# booz_imu_h.net
KiCad netlist of a schematic drawn in EAGLE
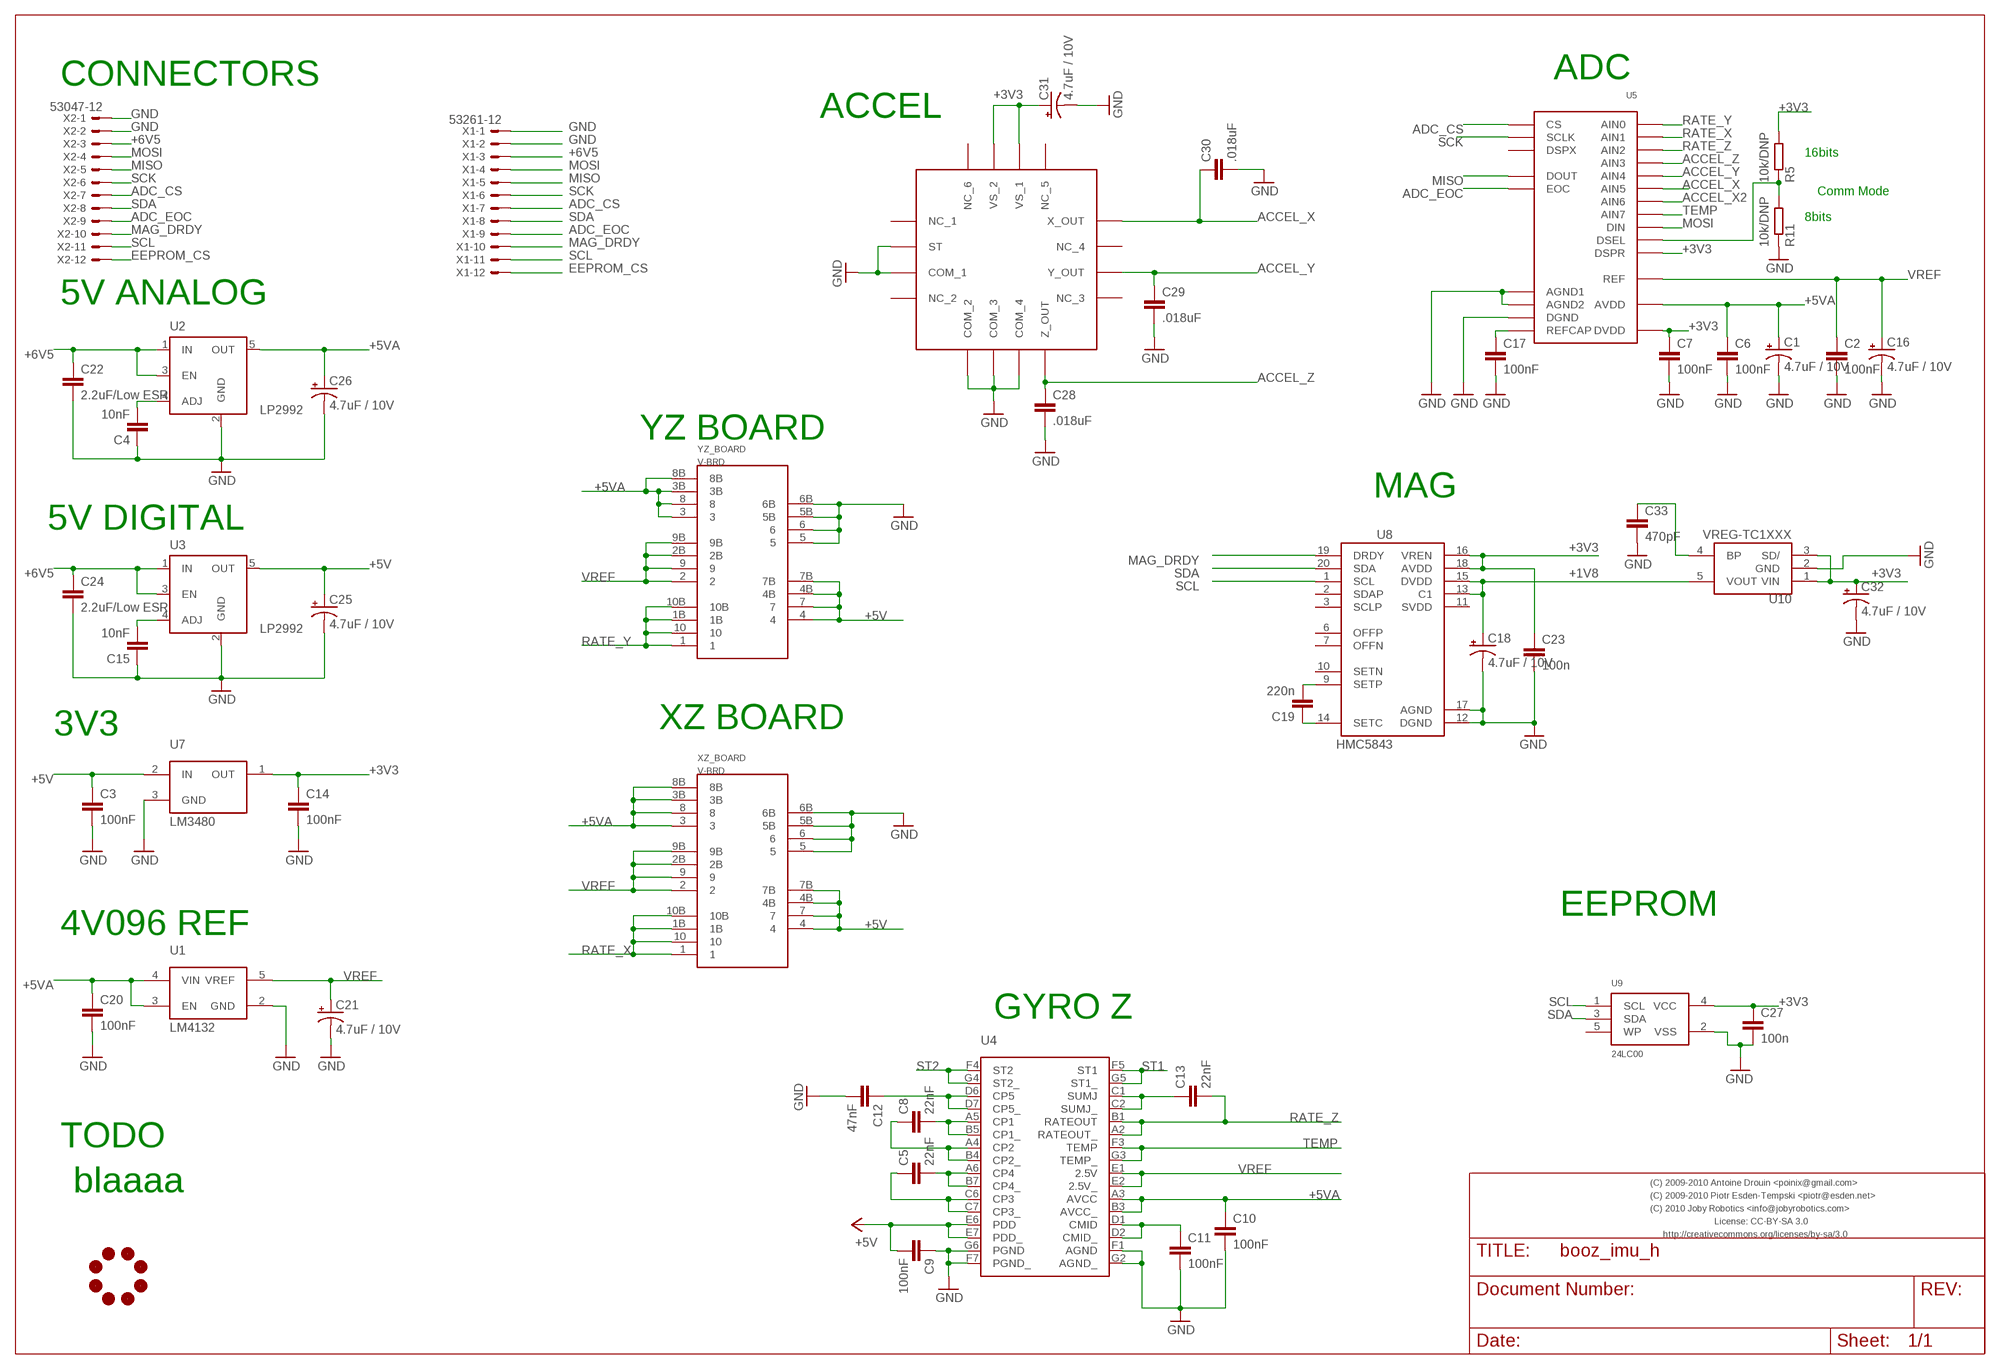
[diagram p0: schematic, sheet 1]

(export (version "E")
  (design (tool "Eeschema 10.0.6"))
  (components
    (comp (ref "C1")
      (value "4.7uF / 10V")
      (footprint "eagle-import:CAP_0805TANT_F95")
      (libsource (lib "eagle-import") (part "CPOL-US"))
    )
    (comp (ref "C2")
      (value "100nF")
      (footprint "eagle-import:0603-CAP")
      (libsource (lib "eagle-import") (part "CAPACITOR-0603"))
    )
    (comp (ref "C3")
      (value "100nF")
      (footprint "eagle-import:0603-CAP")
      (libsource (lib "eagle-import") (part "CAPACITOR-0603"))
    )
    (comp (ref "C4")
      (value "10nF")
      (footprint "eagle-import:0603-CAP")
      (libsource (lib "eagle-import") (part "CAPACITOR-0603"))
    )
    (comp (ref "C5")
      (value "22nF")
      (footprint "eagle-import:0603-CAP")
      (libsource (lib "eagle-import") (part "CAPACITOR-0603"))
    )
    (comp (ref "C6")
      (value "100nF")
      (footprint "eagle-import:0603-CAP")
      (libsource (lib "eagle-import") (part "CAPACITOR-0603"))
    )
    (comp (ref "C7")
      (value "100nF")
      (footprint "eagle-import:0603-CAP")
      (libsource (lib "eagle-import") (part "CAPACITOR-0603"))
    )
    (comp (ref "C8")
      (value "22nF")
      (footprint "eagle-import:0603-CAP")
      (libsource (lib "eagle-import") (part "CAPACITOR-0603"))
    )
    (comp (ref "C9")
      (value "100nF")
      (footprint "eagle-import:0603-CAP")
      (libsource (lib "eagle-import") (part "CAPACITOR-0603"))
    )
    (comp (ref "C10")
      (value "100nF")
      (footprint "eagle-import:0603-CAP")
      (libsource (lib "eagle-import") (part "CAPACITOR-0603"))
    )
    (comp (ref "C11")
      (value "100nF")
      (footprint "eagle-import:0603-CAP")
      (libsource (lib "eagle-import") (part "CAPACITOR-0603"))
    )
    (comp (ref "C12")
      (value "47nF")
      (footprint "eagle-import:0603-CAP")
      (libsource (lib "eagle-import") (part "CAPACITOR-0603"))
    )
    (comp (ref "C13")
      (value "22nF")
      (footprint "eagle-import:0603-CAP")
      (libsource (lib "eagle-import") (part "CAPACITOR-0603"))
    )
    (comp (ref "C14")
      (value "100nF")
      (footprint "eagle-import:0603-CAP")
      (libsource (lib "eagle-import") (part "CAPACITOR-0603"))
    )
    (comp (ref "C15")
      (value "10nF")
      (footprint "eagle-import:0603-CAP")
      (libsource (lib "eagle-import") (part "CAPACITOR-0603"))
    )
    (comp (ref "C16")
      (value "4.7uF / 10V")
      (footprint "eagle-import:CAP_0805TANT_F95")
      (libsource (lib "eagle-import") (part "CPOL-US"))
    )
    (comp (ref "C17")
      (value "100nF")
      (footprint "eagle-import:0603-CAP")
      (libsource (lib "eagle-import") (part "CAPACITOR-0603"))
    )
    (comp (ref "C18")
      (value "4.7uF / 10V")
      (footprint "eagle-import:CAP_0805TANT_F95")
      (libsource (lib "eagle-import") (part "CPOL-US"))
    )
    (comp (ref "C19")
      (value "220n")
      (footprint "eagle-import:0603-CAP")
      (libsource (lib "eagle-import") (part "CAPACITOR-0603"))
    )
    (comp (ref "C20")
      (value "100nF")
      (footprint "eagle-import:0603-CAP")
      (libsource (lib "eagle-import") (part "CAPACITOR-0603"))
    )
    (comp (ref "C21")
      (value "4.7uF / 10V")
      (footprint "eagle-import:CAP_0805TANT_F95")
      (libsource (lib "eagle-import") (part "CPOL-US"))
    )
    (comp (ref "C22")
      (value "2.2uF/Low ESR")
      (footprint "eagle-import:0603-CAP")
      (libsource (lib "eagle-import") (part "CAPACITOR-0603"))
    )
    (comp (ref "C23")
      (value "100n")
      (footprint "eagle-import:0603-CAP")
      (libsource (lib "eagle-import") (part "CAPACITOR-0603"))
    )
    (comp (ref "C24")
      (value "2.2uF/Low ESR")
      (footprint "eagle-import:0603-CAP")
      (libsource (lib "eagle-import") (part "CAPACITOR-0603"))
    )
    (comp (ref "C25")
      (value "4.7uF / 10V")
      (footprint "eagle-import:CAP_0805TANT_F95")
      (libsource (lib "eagle-import") (part "CPOL-US"))
    )
    (comp (ref "C26")
      (value "4.7uF / 10V")
      (footprint "eagle-import:CAP_0805TANT_F95")
      (libsource (lib "eagle-import") (part "CPOL-US"))
    )
    (comp (ref "C27")
      (value "100n")
      (footprint "eagle-import:0603-CAP")
      (libsource (lib "eagle-import") (part "CAPACITOR-0603"))
    )
    (comp (ref "C28")
      (value ".018uF")
      (footprint "eagle-import:0603-CAP")
      (libsource (lib "eagle-import") (part "CAPACITOR-0603"))
    )
    (comp (ref "C29")
      (value ".018uF")
      (footprint "eagle-import:0603-CAP")
      (libsource (lib "eagle-import") (part "CAPACITOR-0603"))
    )
    (comp (ref "C30")
      (value ".018uF")
      (footprint "eagle-import:0603-CAP")
      (libsource (lib "eagle-import") (part "CAPACITOR-0603"))
    )
    (comp (ref "C31")
      (value "4.7uF / 10V")
      (footprint "eagle-import:CAP_0805TANT_F95")
      (libsource (lib "eagle-import") (part "CPOL-US"))
    )
    (comp (ref "C32")
      (value "4.7uF / 10V")
      (footprint "eagle-import:CAP_0805TANT_F95")
      (libsource (lib "eagle-import") (part "CPOL-US"))
    )
    (comp (ref "C33")
      (value "470pF")
      (footprint "eagle-import:0603-CAP")
      (libsource (lib "eagle-import") (part "CAPACITOR-0603"))
    )
    (comp (ref "JL1")
      (value "JOBY_LOGO-6MIL")
      (footprint "eagle-import:JOBY_LOGO_6MIL")
      (libsource (lib "eagle-import") (part "JOBY_LOGO-6MIL"))
    )
    (comp (ref "R5")
      (value "10k/DNP")
      (footprint "eagle-import:0603-RES")
      (libsource (lib "eagle-import") (part "RESISTOR-0603"))
    )
    (comp (ref "R11")
      (value "10k/DNP")
      (footprint "eagle-import:0603-RES")
      (libsource (lib "eagle-import") (part "RESISTOR-0603"))
    )
    (comp (ref "U1")
      (value "LM4132")
      (footprint "eagle-import:SOT23-5L")
      (libsource (lib "eagle-import") (part "LM4132"))
    )
    (comp (ref "U2")
      (value "LP2992")
      (footprint "eagle-import:SOT23-5")
      (libsource (lib "eagle-import") (part "MIC5219BM5"))
    )
    (comp (ref "U3")
      (value "LP2992")
      (footprint "eagle-import:SOT23-5")
      (libsource (lib "eagle-import") (part "MIC5219BM5"))
    )
    (comp (ref "U4")
      (value "ADXR")
      (footprint "eagle-import:BC-32")
      (libsource (lib "eagle-import") (part "ADXR"))
    )
    (comp (ref "U5")
      (value "MAX1168")
      (footprint "eagle-import:QSOP24")
      (libsource (lib "eagle-import") (part "MAX1168"))
    )
    (comp (ref "U6")
      (value "ADXL335")
      (footprint "eagle-import:LFCSP_LQ16")
      (libsource (lib "eagle-import") (part "ADXL335"))
    )
    (comp (ref "U7")
      (value "LM3480")
      (footprint "eagle-import:SOT23")
      (libsource (lib "eagle-import") (part "LM3480"))
    )
    (comp (ref "U8")
      (value "HMC5843")
      (footprint "eagle-import:LPCC20-HMC5843")
      (libsource (lib "eagle-import") (part "HMC5843"))
    )
    (comp (ref "U9")
      (value "24LC00")
      (footprint "eagle-import:SOT23-5")
      (libsource (lib "eagle-import") (part "I2C_EEPROM-SOT23-5"))
    )
    (comp (ref "U10")
      (value "VREG-TC1XXX")
      (footprint "eagle-import:SOT23-5")
      (libsource (lib "eagle-import") (part "VREG-TC1XXX"))
    )
    (comp (ref "X1")
      (value "53261-12")
      (footprint "eagle-import:53261-12")
      (libsource (lib "eagle-import") (part "53?-12261"))
    )
    (comp (ref "X2")
      (value "53047-12")
      (footprint "eagle-import:53047-12")
      (libsource (lib "eagle-import") (part "53?-12047"))
    )
    (comp (ref "XZ_BOARD")
      (value "V-BRD")
      (footprint "eagle-import:V-BRD")
      (libsource (lib "eagle-import") (part "V-BRD"))
    )
    (comp (ref "YZ_BOARD")
      (value "V-BRD")
      (footprint "eagle-import:V-BRD")
      (libsource (lib "eagle-import") (part "V-BRD"))
    )
  )
  (nets
    (net (code "1") (name "+5V") (class "Default")
      (node (ref "C25") (pin "P$1") (pinfunction "+_P$1") (pintype "passive"))
      (node (ref "C3") (pin "P$1") (pinfunction "1_P$1") (pintype "passive"))
      (node (ref "C9") (pin "P$2") (pinfunction "2_P$2") (pintype "passive"))
      (node (ref "U3") (pin "5") (pinfunction "OUT_5") (pintype "output"))
      (node (ref "U4") (pin "E6") (pinfunction "PDD_E6") (pintype "bidirectional"))
      (node (ref "U4") (pin "E7") (pinfunction "PDD__E7") (pintype "bidirectional"))
      (node (ref "U7") (pin "2") (pinfunction "IN_2") (pintype "power_in"))
      (node (ref "XZ_BOARD") (pin "4") (pinfunction "4_4") (pintype "bidirectional"))
      (node (ref "XZ_BOARD") (pin "4B") (pinfunction "4B_4B") (pintype "bidirectional"))
      (node (ref "XZ_BOARD") (pin "7") (pinfunction "7_7") (pintype "bidirectional"))
      (node (ref "XZ_BOARD") (pin "7B") (pinfunction "7B_7B") (pintype "bidirectional"))
      (node (ref "YZ_BOARD") (pin "4") (pinfunction "4_4") (pintype "bidirectional"))
      (node (ref "YZ_BOARD") (pin "4B") (pinfunction "4B_4B") (pintype "bidirectional"))
      (node (ref "YZ_BOARD") (pin "7") (pinfunction "7_7") (pintype "bidirectional"))
      (node (ref "YZ_BOARD") (pin "7B") (pinfunction "7B_7B") (pintype "bidirectional"))
    )
    (net (code "2") (name "/+1V8") (class "Default")
      (node (ref "C18") (pin "P$1") (pinfunction "+_P$1") (pintype "passive"))
      (node (ref "U10") (pin "5") (pinfunction "VOUT_5") (pintype "power_in"))
      (node (ref "U8") (pin "13") (pinfunction "C1_13") (pintype "bidirectional"))
      (node (ref "U8") (pin "15") (pinfunction "DVDD_15") (pintype "bidirectional"))
    )
    (net (code "3") (name "/+3V3") (class "Default")
      (node (ref "C14") (pin "P$1") (pinfunction "1_P$1") (pintype "passive"))
      (node (ref "C23") (pin "P$1") (pinfunction "1_P$1") (pintype "passive"))
      (node (ref "C27") (pin "P$1") (pinfunction "1_P$1") (pintype "passive"))
      (node (ref "C31") (pin "P$1") (pinfunction "+_P$1") (pintype "passive"))
      (node (ref "C32") (pin "P$1") (pinfunction "+_P$1") (pintype "passive"))
      (node (ref "C7") (pin "P$1") (pinfunction "1_P$1") (pintype "passive"))
      (node (ref "R5") (pin "P$2") (pinfunction "2_P$2") (pintype "passive"))
      (node (ref "U10") (pin "1") (pinfunction "VIN_1") (pintype "power_in"))
      (node (ref "U10") (pin "3") (pinfunction "SD/_3") (pintype "input"))
      (node (ref "U5") (pin "P$1") (pinfunction "DSPR_P$1") (pintype "bidirectional"))
      (node (ref "U5") (pin "P$22") (pinfunction "DVDD_P$22") (pintype "bidirectional"))
      (node (ref "U6") (pin "P$14") (pinfunction "VS_1_P$14") (pintype "bidirectional"))
      (node (ref "U6") (pin "P$15") (pinfunction "VS_2_P$15") (pintype "bidirectional"))
      (node (ref "U7") (pin "1") (pinfunction "OUT_1") (pintype "power_in"))
      (node (ref "U8") (pin "16") (pinfunction "VREN_16") (pintype "bidirectional"))
      (node (ref "U8") (pin "18") (pinfunction "AVDD_18") (pintype "bidirectional"))
      (node (ref "U9") (pin "4") (pinfunction "VCC_4") (pintype "bidirectional"))
    )
    (net (code "4") (name "/+5VA") (class "Default")
      (node (ref "C1") (pin "P$1") (pinfunction "+_P$1") (pintype "passive"))
      (node (ref "C10") (pin "P$1") (pinfunction "1_P$1") (pintype "passive"))
      (node (ref "C20") (pin "P$1") (pinfunction "1_P$1") (pintype "passive"))
      (node (ref "C26") (pin "P$1") (pinfunction "+_P$1") (pintype "passive"))
      (node (ref "C6") (pin "P$1") (pinfunction "1_P$1") (pintype "passive"))
      (node (ref "U1") (pin "3") (pinfunction "EN_3") (pintype "bidirectional"))
      (node (ref "U1") (pin "4") (pinfunction "VIN_4") (pintype "power_in"))
      (node (ref "U2") (pin "5") (pinfunction "OUT_5") (pintype "output"))
      (node (ref "U4") (pin "A3") (pinfunction "AVCC_A3") (pintype "bidirectional"))
      (node (ref "U4") (pin "B3") (pinfunction "AVCC__B3") (pintype "bidirectional"))
      (node (ref "U5") (pin "P$19") (pinfunction "AVDD_P$19") (pintype "bidirectional"))
      (node (ref "XZ_BOARD") (pin "3") (pinfunction "3_3") (pintype "bidirectional"))
      (node (ref "XZ_BOARD") (pin "3B") (pinfunction "3B_3B") (pintype "bidirectional"))
      (node (ref "XZ_BOARD") (pin "8") (pinfunction "8_8") (pintype "bidirectional"))
      (node (ref "XZ_BOARD") (pin "8B") (pinfunction "8B_8B") (pintype "bidirectional"))
      (node (ref "YZ_BOARD") (pin "3") (pinfunction "3_3") (pintype "bidirectional"))
      (node (ref "YZ_BOARD") (pin "3B") (pinfunction "3B_3B") (pintype "bidirectional"))
      (node (ref "YZ_BOARD") (pin "8") (pinfunction "8_8") (pintype "bidirectional"))
      (node (ref "YZ_BOARD") (pin "8B") (pinfunction "8B_8B") (pintype "bidirectional"))
    )
    (net (code "5") (name "/+6V5") (class "Default")
      (node (ref "C22") (pin "P$1") (pinfunction "1_P$1") (pintype "passive"))
      (node (ref "C24") (pin "P$1") (pinfunction "1_P$1") (pintype "passive"))
      (node (ref "U2") (pin "1") (pinfunction "IN_1") (pintype "input"))
      (node (ref "U2") (pin "3") (pinfunction "EN_3") (pintype "input"))
      (node (ref "U3") (pin "1") (pinfunction "IN_1") (pintype "input"))
      (node (ref "U3") (pin "3") (pinfunction "EN_3") (pintype "input"))
      (node (ref "X1") (pin "3") (pinfunction "S_3") (pintype "passive"))
      (node (ref "X2") (pin "3") (pinfunction "S_3") (pintype "passive"))
    )
    (net (code "6") (name "/ACCEL_X") (class "Default")
      (node (ref "C30") (pin "P$1") (pinfunction "1_P$1") (pintype "passive"))
      (node (ref "U5") (pin "P$12") (pinfunction "AIN5_P$12") (pintype "bidirectional"))
      (node (ref "U6") (pin "P$12") (pinfunction "X_OUT_P$12") (pintype "bidirectional"))
    )
    (net (code "7") (name "/ACCEL_X2") (class "Default")
      (node (ref "U5") (pin "P$13") (pinfunction "AIN6_P$13") (pintype "bidirectional"))
    )
    (net (code "8") (name "/ACCEL_Y") (class "Default")
      (node (ref "C29") (pin "P$1") (pinfunction "1_P$1") (pintype "passive"))
      (node (ref "U5") (pin "P$11") (pinfunction "AIN4_P$11") (pintype "bidirectional"))
      (node (ref "U6") (pin "P$10") (pinfunction "Y_OUT_P$10") (pintype "bidirectional"))
    )
    (net (code "9") (name "/ACCEL_Z") (class "Default")
      (node (ref "C28") (pin "P$1") (pinfunction "1_P$1") (pintype "passive"))
      (node (ref "U5") (pin "P$10") (pinfunction "AIN3_P$10") (pintype "bidirectional"))
      (node (ref "U6") (pin "P$8") (pinfunction "Z_OUT_P$8") (pintype "bidirectional"))
    )
    (net (code "10") (name "/ADC_CS") (class "Default")
      (node (ref "U5") (pin "P$20") (pinfunction "CS_P$20") (pintype "bidirectional"))
      (node (ref "X1") (pin "7") (pinfunction "S_7") (pintype "passive"))
      (node (ref "X2") (pin "7") (pinfunction "S_7") (pintype "passive"))
    )
    (net (code "11") (name "/ADC_EOC") (class "Default")
      (node (ref "U5") (pin "P$6") (pinfunction "EOC_P$6") (pintype "bidirectional"))
      (node (ref "X1") (pin "9") (pinfunction "S_9") (pintype "passive"))
      (node (ref "X2") (pin "9") (pinfunction "S_9") (pintype "passive"))
    )
    (net (code "12") (name "/EEPROM_CS") (class "Default")
      (node (ref "X1") (pin "12") (pinfunction "S_12") (pintype "passive"))
      (node (ref "X2") (pin "12") (pinfunction "S_12") (pintype "passive"))
    )
    (net (code "13") (name "/MAG_DRDY") (class "Default")
      (node (ref "U8") (pin "19") (pinfunction "DRDY_19") (pintype "bidirectional"))
      (node (ref "X1") (pin "10") (pinfunction "S_10") (pintype "passive"))
      (node (ref "X2") (pin "10") (pinfunction "S_10") (pintype "passive"))
    )
    (net (code "14") (name "/MISO") (class "Default")
      (node (ref "U5") (pin "P$3") (pinfunction "DOUT_P$3") (pintype "bidirectional"))
      (node (ref "X1") (pin "5") (pinfunction "S_5") (pintype "passive"))
      (node (ref "X2") (pin "5") (pinfunction "S_5") (pintype "passive"))
    )
    (net (code "15") (name "/MOSI") (class "Default")
      (node (ref "U5") (pin "P$5") (pinfunction "DIN_P$5") (pintype "bidirectional"))
      (node (ref "X1") (pin "4") (pinfunction "S_4") (pintype "passive"))
      (node (ref "X2") (pin "4") (pinfunction "S_4") (pintype "passive"))
    )
    (net (code "16") (name "/RATE_X") (class "Default")
      (node (ref "U5") (pin "P$8") (pinfunction "AIN1_P$8") (pintype "bidirectional"))
      (node (ref "XZ_BOARD") (pin "1") (pinfunction "1_1") (pintype "bidirectional"))
      (node (ref "XZ_BOARD") (pin "10") (pinfunction "10_10") (pintype "bidirectional"))
      (node (ref "XZ_BOARD") (pin "10B") (pinfunction "10B_10B") (pintype "bidirectional"))
      (node (ref "XZ_BOARD") (pin "1B") (pinfunction "1B_1B") (pintype "bidirectional"))
    )
    (net (code "17") (name "/RATE_Y") (class "Default")
      (node (ref "U5") (pin "P$7") (pinfunction "AIN0_P$7") (pintype "bidirectional"))
      (node (ref "YZ_BOARD") (pin "1") (pinfunction "1_1") (pintype "bidirectional"))
      (node (ref "YZ_BOARD") (pin "10") (pinfunction "10_10") (pintype "bidirectional"))
      (node (ref "YZ_BOARD") (pin "10B") (pinfunction "10B_10B") (pintype "bidirectional"))
      (node (ref "YZ_BOARD") (pin "1B") (pinfunction "1B_1B") (pintype "bidirectional"))
    )
    (net (code "18") (name "/RATE_Z") (class "Default")
      (node (ref "C13") (pin "P$2") (pinfunction "2_P$2") (pintype "passive"))
      (node (ref "U4") (pin "A2") (pinfunction "RATEOUT__A2") (pintype "bidirectional"))
      (node (ref "U4") (pin "B1") (pinfunction "RATEOUT_B1") (pintype "bidirectional"))
      (node (ref "U5") (pin "P$9") (pinfunction "AIN2_P$9") (pintype "bidirectional"))
    )
    (net (code "19") (name "/SCK") (class "Default")
      (node (ref "U5") (pin "P$4") (pinfunction "SCLK_P$4") (pintype "bidirectional"))
      (node (ref "X1") (pin "6") (pinfunction "S_6") (pintype "passive"))
      (node (ref "X2") (pin "6") (pinfunction "S_6") (pintype "passive"))
    )
    (net (code "20") (name "/SCL") (class "Default")
      (node (ref "U8") (pin "1") (pinfunction "SCL_1") (pintype "bidirectional"))
      (node (ref "U9") (pin "1") (pinfunction "SCL_1") (pintype "bidirectional"))
      (node (ref "X1") (pin "11") (pinfunction "S_11") (pintype "passive"))
      (node (ref "X2") (pin "11") (pinfunction "S_11") (pintype "passive"))
    )
    (net (code "21") (name "/SDA") (class "Default")
      (node (ref "U8") (pin "20") (pinfunction "SDA_20") (pintype "bidirectional"))
      (node (ref "U9") (pin "3") (pinfunction "SDA_3") (pintype "bidirectional"))
      (node (ref "X1") (pin "8") (pinfunction "S_8") (pintype "passive"))
      (node (ref "X2") (pin "8") (pinfunction "S_8") (pintype "passive"))
    )
    (net (code "22") (name "/ST1") (class "Default")
      (node (ref "U4") (pin "F5") (pinfunction "ST1_F5") (pintype "bidirectional"))
      (node (ref "U4") (pin "G5") (pinfunction "ST1__G5") (pintype "bidirectional"))
    )
    (net (code "23") (name "/ST2") (class "Default")
      (node (ref "U4") (pin "F4") (pinfunction "ST2_F4") (pintype "bidirectional"))
      (node (ref "U4") (pin "G4") (pinfunction "ST2__G4") (pintype "bidirectional"))
    )
    (net (code "24") (name "/TEMP") (class "Default")
      (node (ref "U4") (pin "F3") (pinfunction "TEMP_F3") (pintype "bidirectional"))
      (node (ref "U4") (pin "G3") (pinfunction "TEMP__G3") (pintype "bidirectional"))
      (node (ref "U5") (pin "P$14") (pinfunction "AIN7_P$14") (pintype "bidirectional"))
    )
    (net (code "25") (name "/VREF") (class "Default")
      (node (ref "C16") (pin "P$1") (pinfunction "+_P$1") (pintype "passive"))
      (node (ref "C2") (pin "P$1") (pinfunction "1_P$1") (pintype "passive"))
      (node (ref "C21") (pin "P$1") (pinfunction "+_P$1") (pintype "passive"))
      (node (ref "U1") (pin "5") (pinfunction "VREF_5") (pintype "power_in"))
      (node (ref "U4") (pin "E1") (pinfunction "2.5V_E1") (pintype "bidirectional"))
      (node (ref "U4") (pin "E2") (pinfunction "2.5V__E2") (pintype "bidirectional"))
      (node (ref "U5") (pin "P$15") (pinfunction "REF_P$15") (pintype "bidirectional"))
      (node (ref "XZ_BOARD") (pin "2") (pinfunction "2_2") (pintype "bidirectional"))
      (node (ref "XZ_BOARD") (pin "2B") (pinfunction "2B_2B") (pintype "bidirectional"))
      (node (ref "XZ_BOARD") (pin "9") (pinfunction "9_9") (pintype "bidirectional"))
      (node (ref "XZ_BOARD") (pin "9B") (pinfunction "9B_9B") (pintype "bidirectional"))
      (node (ref "YZ_BOARD") (pin "2") (pinfunction "2_2") (pintype "bidirectional"))
      (node (ref "YZ_BOARD") (pin "2B") (pinfunction "2B_2B") (pintype "bidirectional"))
      (node (ref "YZ_BOARD") (pin "9") (pinfunction "9_9") (pintype "bidirectional"))
      (node (ref "YZ_BOARD") (pin "9B") (pinfunction "9B_9B") (pintype "bidirectional"))
    )
    (net (code "26") (name "GND") (class "Default")
      (node (ref "C1") (pin "P$2") (pinfunction "-_P$2") (pintype "passive"))
      (node (ref "C10") (pin "P$2") (pinfunction "2_P$2") (pintype "passive"))
      (node (ref "C11") (pin "P$2") (pinfunction "2_P$2") (pintype "passive"))
      (node (ref "C12") (pin "P$2") (pinfunction "2_P$2") (pintype "passive"))
      (node (ref "C14") (pin "P$2") (pinfunction "2_P$2") (pintype "passive"))
      (node (ref "C15") (pin "P$1") (pinfunction "1_P$1") (pintype "passive"))
      (node (ref "C16") (pin "P$2") (pinfunction "-_P$2") (pintype "passive"))
      (node (ref "C17") (pin "P$2") (pinfunction "2_P$2") (pintype "passive"))
      (node (ref "C18") (pin "P$2") (pinfunction "-_P$2") (pintype "passive"))
      (node (ref "C2") (pin "P$2") (pinfunction "2_P$2") (pintype "passive"))
      (node (ref "C20") (pin "P$2") (pinfunction "2_P$2") (pintype "passive"))
      (node (ref "C21") (pin "P$2") (pinfunction "-_P$2") (pintype "passive"))
      (node (ref "C22") (pin "P$2") (pinfunction "2_P$2") (pintype "passive"))
      (node (ref "C23") (pin "P$2") (pinfunction "2_P$2") (pintype "passive"))
      (node (ref "C24") (pin "P$2") (pinfunction "2_P$2") (pintype "passive"))
      (node (ref "C25") (pin "P$2") (pinfunction "-_P$2") (pintype "passive"))
      (node (ref "C26") (pin "P$2") (pinfunction "-_P$2") (pintype "passive"))
      (node (ref "C27") (pin "P$2") (pinfunction "2_P$2") (pintype "passive"))
      (node (ref "C28") (pin "P$2") (pinfunction "2_P$2") (pintype "passive"))
      (node (ref "C29") (pin "P$2") (pinfunction "2_P$2") (pintype "passive"))
      (node (ref "C3") (pin "P$2") (pinfunction "2_P$2") (pintype "passive"))
      (node (ref "C30") (pin "P$2") (pinfunction "2_P$2") (pintype "passive"))
      (node (ref "C31") (pin "P$2") (pinfunction "-_P$2") (pintype "passive"))
      (node (ref "C32") (pin "P$2") (pinfunction "-_P$2") (pintype "passive"))
      (node (ref "C33") (pin "P$2") (pinfunction "2_P$2") (pintype "passive"))
      (node (ref "C4") (pin "P$1") (pinfunction "1_P$1") (pintype "passive"))
      (node (ref "C6") (pin "P$2") (pinfunction "2_P$2") (pintype "passive"))
      (node (ref "C7") (pin "P$2") (pinfunction "2_P$2") (pintype "passive"))
      (node (ref "C9") (pin "P$1") (pinfunction "1_P$1") (pintype "passive"))
      (node (ref "R11") (pin "P$1") (pinfunction "1_P$1") (pintype "passive"))
      (node (ref "U1") (pin "2") (pinfunction "GND_2") (pintype "power_in"))
      (node (ref "U10") (pin "2") (pinfunction "GND_2") (pintype "power_in"))
      (node (ref "U2") (pin "2") (pinfunction "GND_2") (pintype "power_in"))
      (node (ref "U3") (pin "2") (pinfunction "GND_2") (pintype "power_in"))
      (node (ref "U4") (pin "F1") (pinfunction "AGND_F1") (pintype "bidirectional"))
      (node (ref "U4") (pin "F7") (pinfunction "PGND__F7") (pintype "bidirectional"))
      (node (ref "U4") (pin "G2") (pinfunction "AGND__G2") (pintype "bidirectional"))
      (node (ref "U4") (pin "G6") (pinfunction "PGND_G6") (pintype "bidirectional"))
      (node (ref "U5") (pin "P$17") (pinfunction "AGND1_P$17") (pintype "bidirectional"))
      (node (ref "U5") (pin "P$18") (pinfunction "AGND2_P$18") (pintype "bidirectional"))
      (node (ref "U5") (pin "P$21") (pinfunction "DGND_P$21") (pintype "bidirectional"))
      (node (ref "U6") (pin "P$2") (pinfunction "ST_P$2") (pintype "bidirectional"))
      (node (ref "U6") (pin "P$3") (pinfunction "COM_1_P$3") (pintype "bidirectional"))
      (node (ref "U6") (pin "P$5") (pinfunction "COM_2_P$5") (pintype "bidirectional"))
      (node (ref "U6") (pin "P$6") (pinfunction "COM_3_P$6") (pintype "bidirectional"))
      (node (ref "U6") (pin "P$7") (pinfunction "COM_4_P$7") (pintype "bidirectional"))
      (node (ref "U7") (pin "3") (pinfunction "GND_3") (pintype "power_in"))
      (node (ref "U8") (pin "12") (pinfunction "DGND_12") (pintype "bidirectional"))
      (node (ref "U8") (pin "17") (pinfunction "AGND_17") (pintype "bidirectional"))
      (node (ref "U9") (pin "2") (pinfunction "VSS_2") (pintype "bidirectional"))
      (node (ref "X1") (pin "1") (pinfunction "S_1") (pintype "passive"))
      (node (ref "X1") (pin "2") (pinfunction "S_2") (pintype "passive"))
      (node (ref "X2") (pin "1") (pinfunction "S_1") (pintype "passive"))
      (node (ref "X2") (pin "2") (pinfunction "S_2") (pintype "passive"))
      (node (ref "XZ_BOARD") (pin "5") (pinfunction "5_5") (pintype "bidirectional"))
      (node (ref "XZ_BOARD") (pin "5B") (pinfunction "5B_5B") (pintype "bidirectional"))
      (node (ref "XZ_BOARD") (pin "6") (pinfunction "6_6") (pintype "bidirectional"))
      (node (ref "XZ_BOARD") (pin "6B") (pinfunction "6B_6B") (pintype "bidirectional"))
      (node (ref "YZ_BOARD") (pin "5") (pinfunction "5_5") (pintype "bidirectional"))
      (node (ref "YZ_BOARD") (pin "5B") (pinfunction "5B_5B") (pintype "bidirectional"))
      (node (ref "YZ_BOARD") (pin "6") (pinfunction "6_6") (pintype "bidirectional"))
      (node (ref "YZ_BOARD") (pin "6B") (pinfunction "6B_6B") (pintype "bidirectional"))
    )
    (net (code "27") (name "Net-(C4-2)") (class "Default")
      (node (ref "C4") (pin "P$2") (pinfunction "2_P$2") (pintype "passive"))
      (node (ref "U2") (pin "4") (pinfunction "ADJ_4") (pintype "passive"))
    )
    (net (code "28") (name "Net-(C5-1)") (class "Default")
      (node (ref "C5") (pin "P$1") (pinfunction "1_P$1") (pintype "passive"))
      (node (ref "U4") (pin "C6") (pinfunction "CP3_C6") (pintype "bidirectional"))
      (node (ref "U4") (pin "C7") (pinfunction "CP3__C7") (pintype "bidirectional"))
    )
    (net (code "29") (name "Net-(C5-2)") (class "Default")
      (node (ref "C5") (pin "P$2") (pinfunction "2_P$2") (pintype "passive"))
      (node (ref "U4") (pin "A6") (pinfunction "CP4_A6") (pintype "bidirectional"))
      (node (ref "U4") (pin "B7") (pinfunction "CP4__B7") (pintype "bidirectional"))
    )
    (net (code "30") (name "Net-(C8-1)") (class "Default")
      (node (ref "C8") (pin "P$1") (pinfunction "1_P$1") (pintype "passive"))
      (node (ref "U4") (pin "A4") (pinfunction "CP2_A4") (pintype "bidirectional"))
      (node (ref "U4") (pin "B4") (pinfunction "CP2__B4") (pintype "bidirectional"))
    )
    (net (code "31") (name "Net-(C8-2)") (class "Default")
      (node (ref "C8") (pin "P$2") (pinfunction "2_P$2") (pintype "passive"))
      (node (ref "U4") (pin "A5") (pinfunction "CP1_A5") (pintype "bidirectional"))
      (node (ref "U4") (pin "B5") (pinfunction "CP1__B5") (pintype "bidirectional"))
    )
    (net (code "32") (name "Net-(C11-1)") (class "Default")
      (node (ref "C11") (pin "P$1") (pinfunction "1_P$1") (pintype "passive"))
      (node (ref "U4") (pin "D1") (pinfunction "CMID_D1") (pintype "bidirectional"))
      (node (ref "U4") (pin "D2") (pinfunction "CMID__D2") (pintype "bidirectional"))
    )
    (net (code "33") (name "Net-(C12-1)") (class "Default")
      (node (ref "C12") (pin "P$1") (pinfunction "1_P$1") (pintype "passive"))
      (node (ref "U4") (pin "D6") (pinfunction "CP5_D6") (pintype "bidirectional"))
      (node (ref "U4") (pin "D7") (pinfunction "CP5__D7") (pintype "bidirectional"))
    )
    (net (code "34") (name "Net-(C13-1)") (class "Default")
      (node (ref "C13") (pin "P$1") (pinfunction "1_P$1") (pintype "passive"))
      (node (ref "U4") (pin "C1") (pinfunction "SUMJ_C1") (pintype "bidirectional"))
      (node (ref "U4") (pin "C2") (pinfunction "SUMJ__C2") (pintype "bidirectional"))
    )
    (net (code "35") (name "Net-(C15-2)") (class "Default")
      (node (ref "C15") (pin "P$2") (pinfunction "2_P$2") (pintype "passive"))
      (node (ref "U3") (pin "4") (pinfunction "ADJ_4") (pintype "passive"))
    )
    (net (code "36") (name "Net-(C17-1)") (class "Default")
      (node (ref "C17") (pin "P$1") (pinfunction "1_P$1") (pintype "passive"))
      (node (ref "U5") (pin "P$16") (pinfunction "REFCAP_P$16") (pintype "bidirectional"))
    )
    (net (code "37") (name "Net-(C19-1)") (class "Default")
      (node (ref "C19") (pin "P$1") (pinfunction "1_P$1") (pintype "passive"))
      (node (ref "U8") (pin "14") (pinfunction "SETC_14") (pintype "bidirectional"))
    )
    (net (code "38") (name "Net-(C19-2)") (class "Default")
      (node (ref "C19") (pin "P$2") (pinfunction "2_P$2") (pintype "passive"))
      (node (ref "U8") (pin "9") (pinfunction "SETP_9") (pintype "bidirectional"))
    )
    (net (code "39") (name "Net-(C33-1)") (class "Default")
      (node (ref "C33") (pin "P$1") (pinfunction "1_P$1") (pintype "passive"))
      (node (ref "U10") (pin "4") (pinfunction "BP_4") (pintype "passive"))
    )
    (net (code "40") (name "Net-(R11-2)") (class "Default")
      (node (ref "R11") (pin "P$2") (pinfunction "2_P$2") (pintype "passive"))
      (node (ref "R5") (pin "P$1") (pinfunction "1_P$1") (pintype "passive"))
      (node (ref "U5") (pin "P$2") (pinfunction "DSEL_P$2") (pintype "bidirectional"))
    )
    (net (code "41") (name "unconnected-(U5-DSPX-PadP$23)") (class "Default")
      (node (ref "U5") (pin "P$23") (pinfunction "DSPX_P$23") (pintype "bidirectional"))
    )
    (net (code "42") (name "unconnected-(U6-NC_1-PadP$1)") (class "Default")
      (node (ref "U6") (pin "P$1") (pinfunction "NC_1_P$1") (pintype "bidirectional"))
    )
    (net (code "43") (name "unconnected-(U6-NC_2-PadP$4)") (class "Default")
      (node (ref "U6") (pin "P$4") (pinfunction "NC_2_P$4") (pintype "bidirectional"))
    )
    (net (code "44") (name "unconnected-(U6-NC_3-PadP$9)") (class "Default")
      (node (ref "U6") (pin "P$9") (pinfunction "NC_3_P$9") (pintype "bidirectional"))
    )
    (net (code "45") (name "unconnected-(U6-NC_4-PadP$11)") (class "Default")
      (node (ref "U6") (pin "P$11") (pinfunction "NC_4_P$11") (pintype "bidirectional"))
    )
    (net (code "46") (name "unconnected-(U6-NC_5-PadP$13)") (class "Default")
      (node (ref "U6") (pin "P$13") (pinfunction "NC_5_P$13") (pintype "bidirectional"))
    )
    (net (code "47") (name "unconnected-(U6-NC_6-PadP$16)") (class "Default")
      (node (ref "U6") (pin "P$16") (pinfunction "NC_6_P$16") (pintype "bidirectional"))
    )
    (net (code "48") (name "unconnected-(U8-OFFN-Pad7)") (class "Default")
      (node (ref "U8") (pin "7") (pinfunction "OFFN_7") (pintype "bidirectional"))
    )
    (net (code "49") (name "unconnected-(U8-OFFP-Pad6)") (class "Default")
      (node (ref "U8") (pin "6") (pinfunction "OFFP_6") (pintype "bidirectional"))
    )
    (net (code "50") (name "unconnected-(U8-SCLP-Pad3)") (class "Default")
      (node (ref "U8") (pin "3") (pinfunction "SCLP_3") (pintype "bidirectional"))
    )
    (net (code "51") (name "unconnected-(U8-SDAP-Pad2)") (class "Default")
      (node (ref "U8") (pin "2") (pinfunction "SDAP_2") (pintype "bidirectional"))
    )
    (net (code "52") (name "unconnected-(U8-SETN-Pad10)") (class "Default")
      (node (ref "U8") (pin "10") (pinfunction "SETN_10") (pintype "bidirectional"))
    )
    (net (code "53") (name "unconnected-(U8-SVDD-Pad11)") (class "Default")
      (node (ref "U8") (pin "11") (pinfunction "SVDD_11") (pintype "bidirectional"))
    )
    (net (code "54") (name "unconnected-(U9-WP-Pad5)") (class "Default")
      (node (ref "U9") (pin "5") (pinfunction "WP_5") (pintype "bidirectional"))
    )
  )
)
